# EIS_CO2_Power.net
KiCad netlist of a schematic drawn in Altium Designer
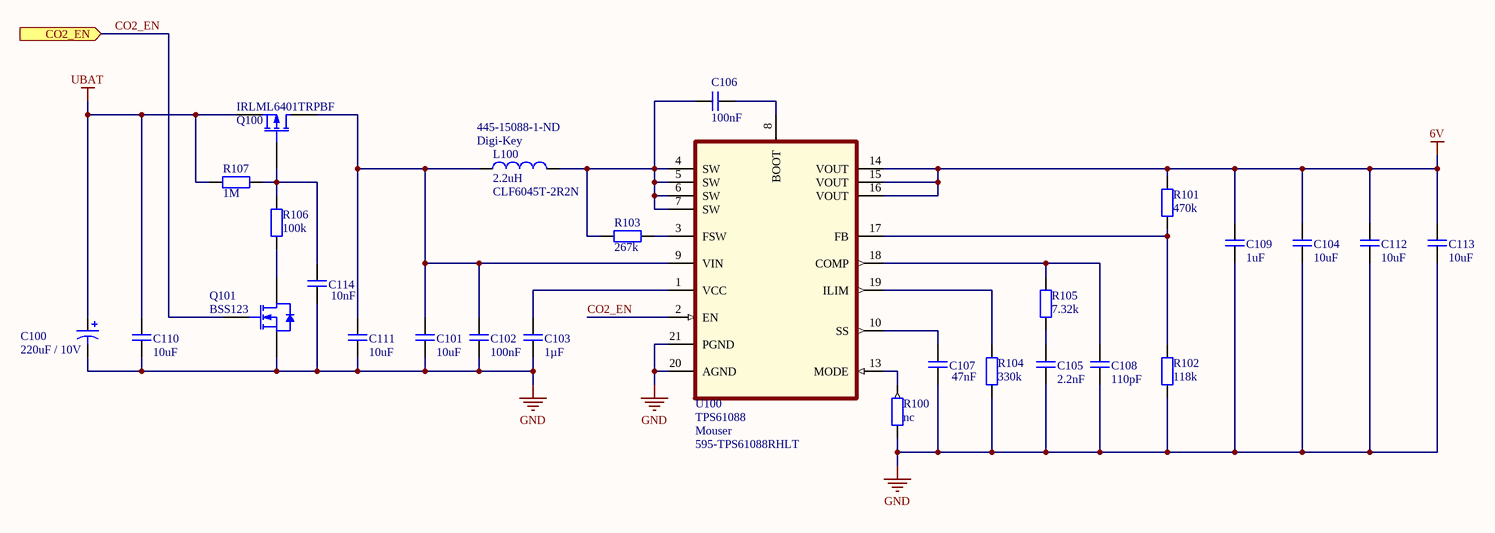
[diagram p0: EIS_CO2_Power.SchDoc]

(export (version "E")
  (design (tool "Eeschema 10.0.6"))
  (components
    (comp (ref "C100")
      (value "220uF / 10V")
      (footprint "D")
      (description "Polarized Capacitor (Surface Mount)")
      (fields (field (name "PUBLISHER") "Altium Limited"))
      (libsource (lib "Miscellaneous Devices") (part "Cap Pol3"))
    )
    (comp (ref "C101")
      (value "10uF")
      (footprint "CAPC3216N")
      (libsource (lib "My_Schlib_6_18") (part "Kondensator SMD Keramik"))
    )
    (comp (ref "C102")
      (value "100nF")
      (footprint "CAPC1608N")
      (libsource (lib "My_Schlib_6_18") (part "Kondensator SMD Keramik"))
    )
    (comp (ref "C103")
      (value "1µF")
      (footprint "CAPC1608N")
      (libsource (lib "My_Schlib_6_18") (part "Kondensator SMD Keramik"))
    )
    (comp (ref "C104")
      (value "10uF")
      (footprint "CAPC3216N")
      (libsource (lib "My_Schlib_6_18") (part "Kondensator SMD Keramik"))
    )
    (comp (ref "C105")
      (value "2.2nF")
      (footprint "CAPC1608N")
      (libsource (lib "My_Schlib_6_18") (part "Kondensator SMD Keramik"))
    )
    (comp (ref "C106")
      (value "100nF")
      (footprint "CAPC1608N")
      (libsource (lib "My_Schlib_6_18") (part "Kondensator SMD Keramik"))
    )
    (comp (ref "C107")
      (value "47nF")
      (footprint "CAPC1608N")
      (libsource (lib "My_Schlib_6_18") (part "Kondensator SMD Keramik"))
    )
    (comp (ref "C108")
      (value "110pF")
      (footprint "CAPC1608N")
      (libsource (lib "My_Schlib_6_18") (part "Kondensator SMD Keramik"))
    )
    (comp (ref "C109")
      (value "1uF")
      (footprint "CAPC3216N")
      (libsource (lib "My_Schlib_6_18") (part "Kondensator SMD Keramik"))
    )
    (comp (ref "C110")
      (value "10uF")
      (footprint "CAPC3216N")
      (libsource (lib "My_Schlib_6_18") (part "Kondensator SMD Keramik"))
    )
    (comp (ref "C111")
      (value "10uF")
      (footprint "CAPC3216N")
      (libsource (lib "My_Schlib_6_18") (part "Kondensator SMD Keramik"))
    )
    (comp (ref "C112")
      (value "10uF")
      (footprint "CAPC3216N")
      (libsource (lib "My_Schlib_6_18") (part "Kondensator SMD Keramik"))
    )
    (comp (ref "C113")
      (value "10uF")
      (footprint "CAPC3216N")
      (libsource (lib "My_Schlib_6_18") (part "Kondensator SMD Keramik"))
    )
    (comp (ref "C114")
      (value "10nF")
      (footprint "CAPC1608N")
      (libsource (lib "My_Schlib_6_18") (part "Kondensator SMD Keramik"))
    )
    (comp (ref "L100")
      (value "2.2uH")
      (footprint "CLF6045")
      (description "Inductor")
      (fields
        (field (name "SUPPLIER PART NUMBER 1") "CLF6045T-2R2N")
        (field (name "SUPPLIER 2") "Digi-Key")
        (field (name "SUPPLIER PART NUMBER 2") "445-15088-1-ND")
        (field (name "Comment") "CLF6045T-2R2N")
        (field (name "PUBLISHER") "Altium Limited")
      )
      (libsource (lib "MetaSensClampOn_BT") (part "Inductor"))
    )
    (comp (ref "Q100")
      (value "IRLML6401TRPBF")
      (footprint "SOT23_N")
      (description "P-Channel MOSFET")
      (fields (field (name "PUBLISHER") "Altium Limited"))
      (libsource (lib "Eis_Lib") (part "IRLML6401TRPBF"))
    )
    (comp (ref "Q101")
      (value "BSS123")
      (footprint "SOT23_N - BSS123")
      (description "N-channel Enhancement Mode Vertical D-MOSFET")
      (fields (field (name "PUBLISHER") "Altium Limited"))
      (libsource (lib "Philips Discrete MOSFET - Low Power") (part "BSS123"))
    )
    (comp (ref "R100")
      (value "nc")
      (footprint "RESC1608N")
      (description "RESC1608 (R0603)")
      (fields (field (name "PUBLISHER") "HSG Jürgen Merz"))
      (libsource (lib "MetaSensClampOn_BT") (part "RESC1608 (R0603)"))
    )
    (comp (ref "R101")
      (value "470k")
      (footprint "RESC1608N")
      (description "RESC1608 (R0603)")
      (fields (field (name "PUBLISHER") "HSG Jürgen Merz"))
      (libsource (lib "MetaSensClampOn_BT") (part "RESC1608 (R0603)"))
    )
    (comp (ref "R102")
      (value "118k")
      (footprint "RESC1608N")
      (description "RESC1608 (R0603)")
      (fields (field (name "PUBLISHER") "HSG Jürgen Merz"))
      (libsource (lib "MetaSensClampOn_BT") (part "RESC1608 (R0603)"))
    )
    (comp (ref "R103")
      (value "267k")
      (footprint "RESC1608N")
      (description "RESC1608 (R0603)")
      (fields (field (name "PUBLISHER") "HSG Jürgen Merz"))
      (libsource (lib "") (part "RESC1608 (R0603)_3"))
    )
    (comp (ref "R104")
      (value "330k")
      (footprint "RESC1608N")
      (description "RESC1608 (R0603)")
      (fields (field (name "PUBLISHER") "HSG Jürgen Merz"))
      (libsource (lib "MetaSensClampOn_BT") (part "RESC1608 (R0603)"))
    )
    (comp (ref "R105")
      (value "7.32k")
      (footprint "RESC1608N")
      (description "RESC1608 (R0603)")
      (fields (field (name "PUBLISHER") "HSG Jürgen Merz"))
      (libsource (lib "MetaSensClampOn_BT") (part "RESC1608 (R0603)"))
    )
    (comp (ref "R106")
      (value "100k")
      (footprint "RESC1608N")
      (description "RESC1608 (R0603)")
      (fields (field (name "PUBLISHER") "HSG Jürgen Merz"))
      (libsource (lib "") (part "RESC1608 (R0603)_1"))
    )
    (comp (ref "R107")
      (value "1M")
      (footprint "RESC1608N")
      (description "RESC1608 (R0603)")
      (fields (field (name "PUBLISHER") "HSG Jürgen Merz"))
      (libsource (lib "") (part "RESC1608 (R0603)_2"))
    )
    (comp (ref "U100")
      (value "TPS61088")
      (footprint "RHL0020A")
      (description "Boost Schaltregler, 2,7V - 12 Uin / 4.5V-12.6V Uout / 3A / 1µA Shutdown")
      (fields (field (name "SUPPLIER 1") "Mouser") (field (name "SUPPLIER PART NUMBER 1") "595-TPS61088RHLT"))
      (libsource (lib "Eis_Lib") (part "TPS61088"))
    )
  )
  (nets
    (net (code "1") (name "/CO2_EN") (class "Default")
      (node (ref "Q101") (pin "1") (pinfunction "G_1") (pintype "passive"))
      (node (ref "U100") (pin "2") (pinfunction "EN_2") (pintype "input"))
    )
    (net (code "2") (name "6V") (class "Default")
      (node (ref "C104") (pin "1") (pinfunction "1_1") (pintype "passive"))
      (node (ref "C109") (pin "1") (pinfunction "1_1") (pintype "passive"))
      (node (ref "C112") (pin "1") (pinfunction "1_1") (pintype "passive"))
      (node (ref "C113") (pin "1") (pinfunction "1_1") (pintype "passive"))
      (node (ref "R101") (pin "1") (pinfunction "1_1") (pintype "passive"))
      (node (ref "U100") (pin "14") (pinfunction "VOUT_14") (pintype "power_in"))
      (node (ref "U100") (pin "15") (pinfunction "VOUT_15") (pintype "power_in"))
      (node (ref "U100") (pin "16") (pinfunction "VOUT_16") (pintype "power_in"))
    )
    (net (code "3") (name "GND") (class "Default")
      (node (ref "C100") (pin "2") (pinfunction "2_2") (pintype "passive"))
      (node (ref "C101") (pin "2") (pinfunction "2_2") (pintype "passive"))
      (node (ref "C102") (pin "1") (pinfunction "1_1") (pintype "passive"))
      (node (ref "C103") (pin "1") (pinfunction "1_1") (pintype "passive"))
      (node (ref "C104") (pin "2") (pinfunction "2_2") (pintype "passive"))
      (node (ref "C105") (pin "1") (pinfunction "1_1") (pintype "passive"))
      (node (ref "C107") (pin "1") (pinfunction "1_1") (pintype "passive"))
      (node (ref "C108") (pin "1") (pinfunction "1_1") (pintype "passive"))
      (node (ref "C109") (pin "2") (pinfunction "2_2") (pintype "passive"))
      (node (ref "C110") (pin "2") (pinfunction "2_2") (pintype "passive"))
      (node (ref "C111") (pin "2") (pinfunction "2_2") (pintype "passive"))
      (node (ref "C112") (pin "2") (pinfunction "2_2") (pintype "passive"))
      (node (ref "C113") (pin "2") (pinfunction "2_2") (pintype "passive"))
      (node (ref "C114") (pin "1") (pinfunction "1_1") (pintype "passive"))
      (node (ref "Q101") (pin "2") (pinfunction "S_2") (pintype "passive"))
      (node (ref "R100") (pin "2") (pinfunction "2_2") (pintype "passive"))
      (node (ref "R102") (pin "2") (pinfunction "2_2") (pintype "passive"))
      (node (ref "R104") (pin "2") (pinfunction "2_2") (pintype "passive"))
      (node (ref "U100") (pin "20") (pinfunction "AGND_20") (pintype "power_in"))
      (node (ref "U100") (pin "21") (pinfunction "PGND_21") (pintype "power_in"))
    )
    (net (code "4") (name "Net-(C105-Pad2)") (class "Default")
      (node (ref "C105") (pin "2") (pinfunction "2_2") (pintype "passive"))
      (node (ref "R105") (pin "2") (pinfunction "2_2") (pintype "passive"))
    )
    (net (code "5") (name "Net-(C106-Pad1)") (class "Default")
      (node (ref "C106") (pin "1") (pinfunction "1_1") (pintype "passive"))
      (node (ref "L100") (pin "2") (pinfunction "2_2") (pintype "passive"))
      (node (ref "R103") (pin "2") (pinfunction "2_2") (pintype "passive"))
      (node (ref "U100") (pin "4") (pinfunction "SW_4") (pintype "passive"))
      (node (ref "U100") (pin "5") (pinfunction "SW_5") (pintype "passive"))
      (node (ref "U100") (pin "6") (pinfunction "SW_6") (pintype "passive"))
      (node (ref "U100") (pin "7") (pinfunction "SW_7") (pintype "passive"))
    )
    (net (code "6") (name "Net-(Q100-D)") (class "Default")
      (node (ref "C101") (pin "1") (pinfunction "1_1") (pintype "passive"))
      (node (ref "C102") (pin "2") (pinfunction "2_2") (pintype "passive"))
      (node (ref "C111") (pin "1") (pinfunction "1_1") (pintype "passive"))
      (node (ref "L100") (pin "1") (pinfunction "1_1") (pintype "passive"))
      (node (ref "Q100") (pin "3") (pinfunction "D_3") (pintype "passive"))
      (node (ref "U100") (pin "9") (pinfunction "VIN_9") (pintype "power_in"))
    )
    (net (code "7") (name "Net-(Q100-G)") (class "Default")
      (node (ref "C114") (pin "2") (pinfunction "2_2") (pintype "passive"))
      (node (ref "Q100") (pin "1") (pinfunction "G_1") (pintype "passive"))
      (node (ref "R106") (pin "2") (pinfunction "2_2") (pintype "passive"))
      (node (ref "R107") (pin "2") (pinfunction "2_2") (pintype "passive"))
    )
    (net (code "8") (name "Net-(Q101-D)") (class "Default")
      (node (ref "Q101") (pin "3") (pinfunction "D_3") (pintype "passive"))
      (node (ref "R106") (pin "1") (pinfunction "1_1") (pintype "passive"))
    )
    (net (code "9") (name "Net-(U100-BOOT)") (class "Default")
      (node (ref "C106") (pin "2") (pinfunction "2_2") (pintype "passive"))
      (node (ref "U100") (pin "8") (pinfunction "BOOT_8") (pintype "passive"))
    )
    (net (code "10") (name "Net-(U100-COMP)") (class "Default")
      (node (ref "C108") (pin "2") (pinfunction "2_2") (pintype "passive"))
      (node (ref "R105") (pin "1") (pinfunction "1_1") (pintype "passive"))
      (node (ref "U100") (pin "18") (pinfunction "COMP_18") (pintype "output"))
    )
    (net (code "11") (name "Net-(U100-FB)") (class "Default")
      (node (ref "R101") (pin "2") (pinfunction "2_2") (pintype "passive"))
      (node (ref "R102") (pin "1") (pinfunction "1_1") (pintype "passive"))
      (node (ref "U100") (pin "17") (pinfunction "FB_17") (pintype "passive"))
    )
    (net (code "12") (name "Net-(U100-FSW)") (class "Default")
      (node (ref "R103") (pin "1") (pinfunction "1_1") (pintype "passive"))
      (node (ref "U100") (pin "3") (pinfunction "FSW_3") (pintype "passive"))
    )
    (net (code "13") (name "Net-(U100-ILIM)") (class "Default")
      (node (ref "R104") (pin "1") (pinfunction "1_1") (pintype "passive"))
      (node (ref "U100") (pin "19") (pinfunction "ILIM_19") (pintype "output"))
    )
    (net (code "14") (name "Net-(U100-MODE)") (class "Default")
      (node (ref "R100") (pin "1") (pinfunction "1_1") (pintype "passive"))
      (node (ref "U100") (pin "13") (pinfunction "MODE_13") (pintype "input"))
    )
    (net (code "15") (name "Net-(U100-SS)") (class "Default")
      (node (ref "C107") (pin "2") (pinfunction "2_2") (pintype "passive"))
      (node (ref "U100") (pin "10") (pinfunction "SS_10") (pintype "output"))
    )
    (net (code "16") (name "Net-(U100-VCC)") (class "Default")
      (node (ref "C103") (pin "2") (pinfunction "2_2") (pintype "passive"))
      (node (ref "U100") (pin "1") (pinfunction "VCC_1") (pintype "passive"))
    )
    (net (code "17") (name "UBAT") (class "Default")
      (node (ref "C100") (pin "1") (pinfunction "1_1") (pintype "passive"))
      (node (ref "C110") (pin "1") (pinfunction "1_1") (pintype "passive"))
      (node (ref "Q100") (pin "2") (pinfunction "S_2") (pintype "passive"))
      (node (ref "R107") (pin "1") (pinfunction "1_1") (pintype "passive"))
    )
  )
)
